# wa_psu.net
KiCad netlist of a schematic drawn in EAGLE
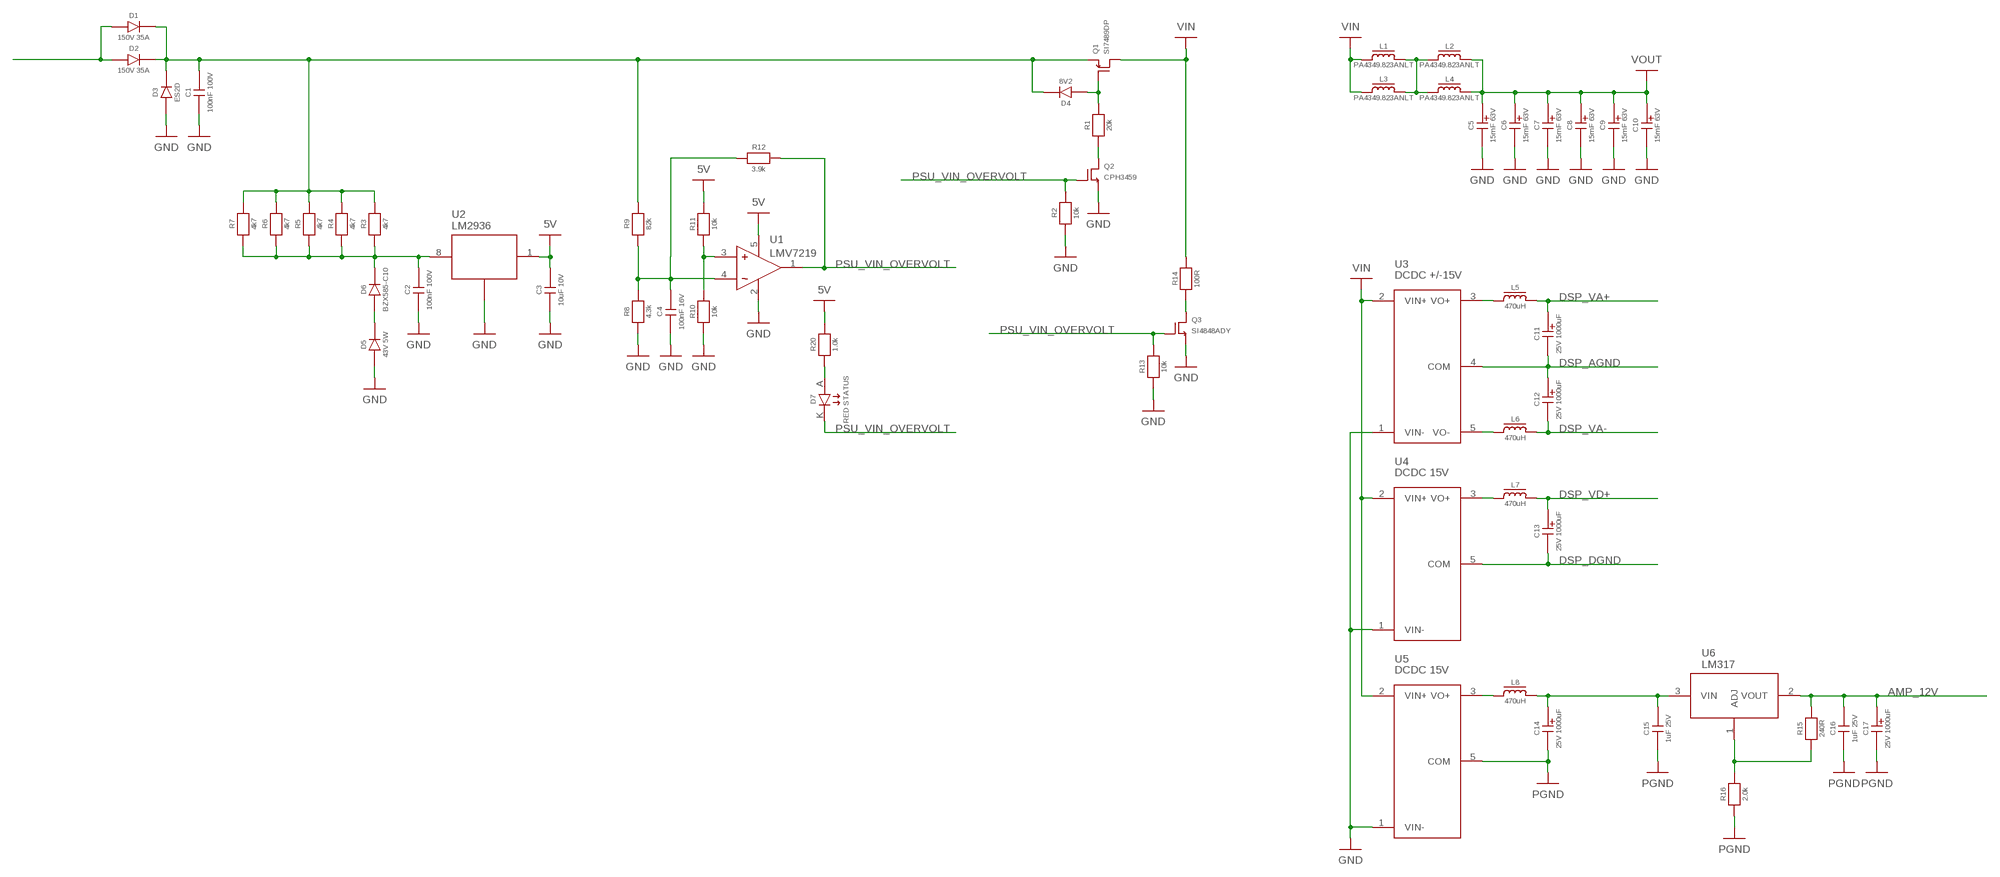
[diagram p0: schematic, sheet 1]

(export (version "E")
  (design (tool "Eeschema 10.0.6"))
  (components
    (comp (ref "C1")
      (value "100nF 100V")
      (footprint "eagle-import:0603")
      (libsource (lib "eagle-import") (part "06031C104KAT2A"))
    )
    (comp (ref "C2")
      (value "100nF 100V")
      (footprint "eagle-import:0603")
      (libsource (lib "eagle-import") (part "06031C104KAT2A"))
    )
    (comp (ref "C3")
      (value "10uF 10V")
      (footprint "eagle-import:0603")
      (libsource (lib "eagle-import") (part "GRM188R61A106KE69D"))
    )
    (comp (ref "C4")
      (value "100nF 16V")
      (footprint "eagle-import:0603")
      (libsource (lib "eagle-import") (part "CL10B104KO8WPNC"))
    )
    (comp (ref "C5")
      (value "15mF 63V")
      (footprint "eagle-import:35MM_10MMCAP")
      (libsource (lib "eagle-import") (part "C_ELEC35MM"))
    )
    (comp (ref "C6")
      (value "15mF 63V")
      (footprint "eagle-import:35MM_10MMCAP")
      (libsource (lib "eagle-import") (part "C_ELEC35MM"))
    )
    (comp (ref "C7")
      (value "15mF 63V")
      (footprint "eagle-import:35MM_10MMCAP")
      (libsource (lib "eagle-import") (part "C_ELEC35MM"))
    )
    (comp (ref "C8")
      (value "15mF 63V")
      (footprint "eagle-import:35MM_10MMCAP")
      (libsource (lib "eagle-import") (part "C_ELEC35MM"))
    )
    (comp (ref "C9")
      (value "15mF 63V")
      (footprint "eagle-import:35MM_10MMCAP")
      (libsource (lib "eagle-import") (part "C_ELEC35MM"))
    )
    (comp (ref "C10")
      (value "15mF 63V")
      (footprint "eagle-import:35MM_10MMCAP")
      (libsource (lib "eagle-import") (part "C_ELEC35MM"))
    )
    (comp (ref "C11")
      (value "25V 1000uF")
      (footprint "eagle-import:10MM_RADIAL_5MM_PITCH")
      (libsource (lib "eagle-import") (part "25ZLJ1000M10X20"))
    )
    (comp (ref "C12")
      (value "25V 1000uF")
      (footprint "eagle-import:10MM_RADIAL_5MM_PITCH")
      (libsource (lib "eagle-import") (part "25ZLJ1000M10X20"))
    )
    (comp (ref "C13")
      (value "25V 1000uF")
      (footprint "eagle-import:10MM_RADIAL_5MM_PITCH")
      (libsource (lib "eagle-import") (part "25ZLJ1000M10X20"))
    )
    (comp (ref "C14")
      (value "25V 1000uF")
      (footprint "eagle-import:10MM_RADIAL_5MM_PITCH")
      (libsource (lib "eagle-import") (part "25ZLJ1000M10X20"))
    )
    (comp (ref "C15")
      (value "1uF 25V")
      (footprint "eagle-import:0603")
      (libsource (lib "eagle-import") (part "CL10A105KA8NNNC"))
    )
    (comp (ref "C16")
      (value "1uF 25V")
      (footprint "eagle-import:0603")
      (libsource (lib "eagle-import") (part "CL10A105KA8NNNC"))
    )
    (comp (ref "C17")
      (value "25V 1000uF")
      (footprint "eagle-import:10MM_RADIAL_5MM_PITCH")
      (libsource (lib "eagle-import") (part "25ZLJ1000M10X20"))
    )
    (comp (ref "D1")
      (value "150V 35A")
      (footprint "eagle-import:TO252")
      (libsource (lib "eagle-import") (part "V35PW15-M3/I"))
    )
    (comp (ref "D2")
      (value "150V 35A")
      (footprint "eagle-import:TO252")
      (libsource (lib "eagle-import") (part "V35PW15-M3/I"))
    )
    (comp (ref "D3")
      (value "ES2D")
      (footprint "eagle-import:DO214AA")
      (libsource (lib "eagle-import") (part "ES2D"))
    )
    (comp (ref "D4")
      (value "8V2")
      (footprint "eagle-import:SOD80")
      (libsource (lib "eagle-import") (part "BZT55C8V2"))
    )
    (comp (ref "D5")
      (value "43V 5W")
      (footprint "eagle-import:017AA-01")
      (libsource (lib "eagle-import") (part "1N5367BG"))
    )
    (comp (ref "D6")
      (value "BZX585-C10")
      (footprint "eagle-import:SOD_523")
      (libsource (lib "eagle-import") (part "BZX585-C10"))
    )
    (comp (ref "D7")
      (value "RED STATUS")
      (footprint "eagle-import:VLMT3100")
      (libsource (lib "eagle-import") (part "VLMT3100-GS08"))
    )
    (comp (ref "L1")
      (value "PA4349.823ANLT")
      (footprint "eagle-import:PA4349.ZZZANLT")
      (libsource (lib "eagle-import") (part "PA4349.823ANLT"))
    )
    (comp (ref "L2")
      (value "PA4349.823ANLT")
      (footprint "eagle-import:PA4349.ZZZANLT")
      (libsource (lib "eagle-import") (part "PA4349.823ANLT"))
    )
    (comp (ref "L3")
      (value "PA4349.823ANLT")
      (footprint "eagle-import:PA4349.ZZZANLT")
      (libsource (lib "eagle-import") (part "PA4349.823ANLT"))
    )
    (comp (ref "L4")
      (value "PA4349.823ANLT")
      (footprint "eagle-import:PA4349.ZZZANLT")
      (libsource (lib "eagle-import") (part "PA4349.823ANLT"))
    )
    (comp (ref "L5")
      (value "470uH")
      (footprint "eagle-import:SRN1060")
      (libsource (lib "eagle-import") (part "SRN1060-471M"))
    )
    (comp (ref "L6")
      (value "470uH")
      (footprint "eagle-import:SRN1060")
      (libsource (lib "eagle-import") (part "SRN1060-471M"))
    )
    (comp (ref "L7")
      (value "470uH")
      (footprint "eagle-import:SRN1060")
      (libsource (lib "eagle-import") (part "SRN1060-471M"))
    )
    (comp (ref "L8")
      (value "470uH")
      (footprint "eagle-import:SRN1060")
      (libsource (lib "eagle-import") (part "SRN1060-471M"))
    )
    (comp (ref "Q1")
      (value "SI7489DP")
      (footprint "eagle-import:SO8_POWERPAK")
      (libsource (lib "eagle-import") (part "SI7489DP-T1-E3"))
    )
    (comp (ref "Q2")
      (value "CPH3459")
      (footprint "eagle-import:SOT23-3")
      (libsource (lib "eagle-import") (part "CPH3459-TL-W"))
    )
    (comp (ref "Q3")
      (value "SI4848ADY")
      (footprint "eagle-import:SO8")
      (libsource (lib "eagle-import") (part "SI4848ADY-T1-GE3"))
    )
    (comp (ref "R1")
      (value "20k")
      (footprint "eagle-import:0603")
      (libsource (lib "eagle-import") (part "ERJ3EKF2002V"))
    )
    (comp (ref "R2")
      (value "10k")
      (footprint "eagle-import:0603")
      (libsource (lib "eagle-import") (part "ERJ3EKF1002V"))
    )
    (comp (ref "R3")
      (value "4k7")
      (footprint "eagle-import:1206")
      (libsource (lib "eagle-import") (part "CRCW12064K70FKEAHP"))
    )
    (comp (ref "R4")
      (value "4k7")
      (footprint "eagle-import:1206")
      (libsource (lib "eagle-import") (part "CRCW12064K70FKEAHP"))
    )
    (comp (ref "R5")
      (value "4k7")
      (footprint "eagle-import:1206")
      (libsource (lib "eagle-import") (part "CRCW12064K70FKEAHP"))
    )
    (comp (ref "R6")
      (value "4k7")
      (footprint "eagle-import:1206")
      (libsource (lib "eagle-import") (part "CRCW12064K70FKEAHP"))
    )
    (comp (ref "R7")
      (value "4k7")
      (footprint "eagle-import:1206")
      (libsource (lib "eagle-import") (part "CRCW12064K70FKEAHP"))
    )
    (comp (ref "R8")
      (value "4.3k")
      (footprint "eagle-import:0603")
      (libsource (lib "eagle-import") (part "ERJ3EKF4301V"))
    )
    (comp (ref "R9")
      (value "82k")
      (footprint "eagle-import:0603")
      (libsource (lib "eagle-import") (part "ERJ3EKF8202V"))
    )
    (comp (ref "R10")
      (value "10k")
      (footprint "eagle-import:0603")
      (libsource (lib "eagle-import") (part "ERJ3EKF1002V"))
    )
    (comp (ref "R11")
      (value "10k")
      (footprint "eagle-import:0603")
      (libsource (lib "eagle-import") (part "ERJ3EKF1002V"))
    )
    (comp (ref "R12")
      (value "3.9k")
      (footprint "eagle-import:0603")
      (libsource (lib "eagle-import") (part "ERJ3EKF3901V"))
    )
    (comp (ref "R13")
      (value "10k")
      (footprint "eagle-import:0603")
      (libsource (lib "eagle-import") (part "ERJ3EKF1002V"))
    )
    (comp (ref "R14")
      (value "100R")
      (footprint "eagle-import:15MM_TH")
      (libsource (lib "eagle-import") (part "ERG-3SJ101V"))
    )
    (comp (ref "R15")
      (value "240R")
      (footprint "eagle-import:0603")
      (libsource (lib "eagle-import") (part "ERJ3EKF2400V"))
    )
    (comp (ref "R16")
      (value "2.0k")
      (footprint "eagle-import:0603")
      (libsource (lib "eagle-import") (part "ERJ3EKF2001V"))
    )
    (comp (ref "R20")
      (value "1.0k")
      (footprint "eagle-import:0402")
      (libsource (lib "eagle-import") (part "ERJ-2RKF1001X"))
    )
    (comp (ref "U1")
      (value "LMV7219")
      (footprint "eagle-import:SOT23-5")
      (libsource (lib "eagle-import") (part "LMV7219M5/NOPB"))
    )
    (comp (ref "U2")
      (value "LM2936")
      (footprint "eagle-import:SO8")
      (libsource (lib "eagle-import") (part "LM2936HVMAX"))
    )
    (comp (ref "U3")
      (value "DCDC +/-15V")
      (footprint "eagle-import:PDQE10")
      (libsource (lib "eagle-import") (part "PDQE10-Q48-D15-D"))
    )
    (comp (ref "U4")
      (value "DCDC 15V")
      (footprint "eagle-import:PDQE10")
      (libsource (lib "eagle-import") (part "PDQE10-Q48-S15"))
    )
    (comp (ref "U5")
      (value "DCDC 15V")
      (footprint "eagle-import:PDQE10")
      (libsource (lib "eagle-import") (part "PDQE10-Q48-S15"))
    )
    (comp (ref "U6")
      (value "LM317")
      (footprint "eagle-import:TO220")
      (libsource (lib "eagle-import") (part "LM317T"))
    )
  )
  (nets
    (net (code "1") (name "/AMP_12V") (class "Default")
      (node (ref "C16") (pin "2") (pinfunction "2_2") (pintype "bidirectional"))
      (node (ref "C17") (pin "2") (pinfunction "A_2") (pintype "bidirectional"))
      (node (ref "R15") (pin "2") (pinfunction "2_2") (pintype "bidirectional"))
      (node (ref "U6") (pin "2") (pinfunction "VOUT_2") (pintype "bidirectional"))
    )
    (net (code "2") (name "/DSP_AGND") (class "Default")
      (node (ref "C11") (pin "1") (pinfunction "K_1") (pintype "bidirectional"))
      (node (ref "C12") (pin "2") (pinfunction "A_2") (pintype "bidirectional"))
      (node (ref "U3") (pin "4") (pinfunction "COM_4") (pintype "bidirectional"))
    )
    (net (code "3") (name "/DSP_DGND") (class "Default")
      (node (ref "C13") (pin "1") (pinfunction "K_1") (pintype "bidirectional"))
      (node (ref "U4") (pin "5") (pinfunction "COM_5") (pintype "bidirectional"))
    )
    (net (code "4") (name "/DSP_VA+") (class "Default")
      (node (ref "C11") (pin "2") (pinfunction "A_2") (pintype "bidirectional"))
      (node (ref "L5") (pin "2") (pinfunction "2_2") (pintype "bidirectional"))
    )
    (net (code "5") (name "/DSP_VA-") (class "Default")
      (node (ref "C12") (pin "1") (pinfunction "K_1") (pintype "bidirectional"))
      (node (ref "L6") (pin "2") (pinfunction "2_2") (pintype "bidirectional"))
    )
    (net (code "6") (name "/DSP_VD+") (class "Default")
      (node (ref "C13") (pin "2") (pinfunction "A_2") (pintype "bidirectional"))
      (node (ref "L7") (pin "2") (pinfunction "2_2") (pintype "bidirectional"))
    )
    (net (code "7") (name "/PSU_VIN_OVERVOLT") (class "Default")
      (node (ref "D7") (pin "K") (pinfunction "K_K") (pintype "bidirectional"))
      (node (ref "Q2") (pin "1") (pinfunction "G_1") (pintype "bidirectional"))
      (node (ref "Q3") (pin "4") (pinfunction "G_4") (pintype "bidirectional"))
      (node (ref "R12") (pin "2") (pinfunction "2_2") (pintype "bidirectional"))
      (node (ref "R13") (pin "2") (pinfunction "2_2") (pintype "bidirectional"))
      (node (ref "R2") (pin "2") (pinfunction "2_2") (pintype "bidirectional"))
      (node (ref "U1") (pin "1") (pinfunction "VOUT_1") (pintype "bidirectional"))
    )
    (net (code "8") (name "5V") (class "Default")
      (node (ref "C3") (pin "2") (pinfunction "2_2") (pintype "bidirectional"))
      (node (ref "R11") (pin "2") (pinfunction "2_2") (pintype "bidirectional"))
      (node (ref "R20") (pin "2") (pinfunction "2_2") (pintype "bidirectional"))
      (node (ref "U1") (pin "5") (pinfunction "VCC_5") (pintype "bidirectional"))
      (node (ref "U2") (pin "1") (pinfunction "VOUT_1") (pintype "bidirectional"))
    )
    (net (code "9") (name "GND") (class "Default")
      (node (ref "C1") (pin "1") (pinfunction "1_1") (pintype "bidirectional"))
      (node (ref "C10") (pin "P$2") (pinfunction "2_P$2") (pintype "bidirectional"))
      (node (ref "C2") (pin "1") (pinfunction "1_1") (pintype "bidirectional"))
      (node (ref "C3") (pin "1") (pinfunction "1_1") (pintype "bidirectional"))
      (node (ref "C4") (pin "1") (pinfunction "1_1") (pintype "bidirectional"))
      (node (ref "C5") (pin "P$2") (pinfunction "2_P$2") (pintype "bidirectional"))
      (node (ref "C6") (pin "P$2") (pinfunction "2_P$2") (pintype "bidirectional"))
      (node (ref "C7") (pin "P$2") (pinfunction "2_P$2") (pintype "bidirectional"))
      (node (ref "C8") (pin "P$2") (pinfunction "2_P$2") (pintype "bidirectional"))
      (node (ref "C9") (pin "P$2") (pinfunction "2_P$2") (pintype "bidirectional"))
      (node (ref "D3") (pin "A") (pinfunction "A_A") (pintype "bidirectional"))
      (node (ref "D5") (pin "A") (pinfunction "A_A") (pintype "bidirectional"))
      (node (ref "Q2") (pin "3") (pinfunction "S_3") (pintype "bidirectional"))
      (node (ref "Q3") (pin "1") (pinfunction "S_1") (pintype "bidirectional"))
      (node (ref "Q3") (pin "2") (pinfunction "S_2") (pintype "bidirectional"))
      (node (ref "Q3") (pin "3") (pinfunction "S_3") (pintype "bidirectional"))
      (node (ref "R10") (pin "1") (pinfunction "1_1") (pintype "bidirectional"))
      (node (ref "R13") (pin "1") (pinfunction "1_1") (pintype "bidirectional"))
      (node (ref "R2") (pin "1") (pinfunction "1_1") (pintype "bidirectional"))
      (node (ref "R8") (pin "1") (pinfunction "1_1") (pintype "bidirectional"))
      (node (ref "U1") (pin "2") (pinfunction "GND_2") (pintype "bidirectional"))
      (node (ref "U2") (pin "2") (pinfunction "GND_2") (pintype "bidirectional"))
      (node (ref "U2") (pin "3") (pinfunction "GND_3") (pintype "bidirectional"))
      (node (ref "U2") (pin "6") (pinfunction "GND_6") (pintype "bidirectional"))
      (node (ref "U2") (pin "7") (pinfunction "GND_7") (pintype "bidirectional"))
      (node (ref "U3") (pin "1") (pinfunction "VIN-_1") (pintype "bidirectional"))
      (node (ref "U4") (pin "1") (pinfunction "VIN-_1") (pintype "bidirectional"))
      (node (ref "U5") (pin "1") (pinfunction "VIN-_1") (pintype "bidirectional"))
    )
    (net (code "10") (name "Net-(C14-A)") (class "Default")
      (node (ref "C14") (pin "2") (pinfunction "A_2") (pintype "bidirectional"))
      (node (ref "C15") (pin "2") (pinfunction "2_2") (pintype "bidirectional"))
      (node (ref "L8") (pin "2") (pinfunction "2_2") (pintype "bidirectional"))
      (node (ref "U6") (pin "3") (pinfunction "VIN_3") (pintype "bidirectional"))
    )
    (net (code "11") (name "Net-(D1-A-Pad1)") (class "Default")
      (node (ref "D1") (pin "1") (pinfunction "A_1") (pintype "bidirectional"))
      (node (ref "D1") (pin "3") (pinfunction "A_3") (pintype "bidirectional"))
      (node (ref "D2") (pin "1") (pinfunction "A_1") (pintype "bidirectional"))
      (node (ref "D2") (pin "3") (pinfunction "A_3") (pintype "bidirectional"))
    )
    (net (code "12") (name "Net-(D1-K)") (class "Default")
      (node (ref "C1") (pin "2") (pinfunction "2_2") (pintype "bidirectional"))
      (node (ref "D1") (pin "4") (pinfunction "K_4") (pintype "bidirectional"))
      (node (ref "D2") (pin "4") (pinfunction "K_4") (pintype "bidirectional"))
      (node (ref "D3") (pin "K") (pinfunction "K_K") (pintype "bidirectional"))
      (node (ref "D4") (pin "K") (pinfunction "K_K") (pintype "bidirectional"))
      (node (ref "Q1") (pin "1") (pinfunction "S_1") (pintype "bidirectional"))
      (node (ref "Q1") (pin "2") (pinfunction "S_2") (pintype "bidirectional"))
      (node (ref "Q1") (pin "3") (pinfunction "S_3") (pintype "bidirectional"))
      (node (ref "R3") (pin "2") (pinfunction "2_2") (pintype "bidirectional"))
      (node (ref "R4") (pin "2") (pinfunction "2_2") (pintype "bidirectional"))
      (node (ref "R5") (pin "2") (pinfunction "2_2") (pintype "bidirectional"))
      (node (ref "R6") (pin "2") (pinfunction "2_2") (pintype "bidirectional"))
      (node (ref "R7") (pin "2") (pinfunction "2_2") (pintype "bidirectional"))
      (node (ref "R9") (pin "2") (pinfunction "2_2") (pintype "bidirectional"))
    )
    (net (code "13") (name "Net-(D5-PadK)") (class "Default")
      (node (ref "D5") (pin "K") (pinfunction "K_K") (pintype "bidirectional"))
      (node (ref "D6") (pin "A") (pinfunction "A_A") (pintype "bidirectional"))
    )
    (net (code "14") (name "Net-(D7-PadA)") (class "Default")
      (node (ref "D7") (pin "A") (pinfunction "A_A") (pintype "bidirectional"))
      (node (ref "R20") (pin "1") (pinfunction "1_1") (pintype "bidirectional"))
    )
    (net (code "15") (name "Net-(L1-Pad2)") (class "Default")
      (node (ref "L1") (pin "2") (pinfunction "2_2") (pintype "bidirectional"))
      (node (ref "L2") (pin "1") (pinfunction "1_1") (pintype "bidirectional"))
      (node (ref "L3") (pin "2") (pinfunction "2_2") (pintype "bidirectional"))
      (node (ref "L4") (pin "1") (pinfunction "1_1") (pintype "bidirectional"))
    )
    (net (code "16") (name "Net-(Q1-G)") (class "Default")
      (node (ref "D4") (pin "A") (pinfunction "A_A") (pintype "bidirectional"))
      (node (ref "Q1") (pin "4") (pinfunction "G_4") (pintype "bidirectional"))
      (node (ref "R1") (pin "2") (pinfunction "2_2") (pintype "bidirectional"))
    )
    (net (code "17") (name "Net-(Q2-D)") (class "Default")
      (node (ref "Q2") (pin "2") (pinfunction "D_2") (pintype "bidirectional"))
      (node (ref "R1") (pin "1") (pinfunction "1_1") (pintype "bidirectional"))
    )
    (net (code "18") (name "Net-(Q3-D-Pad5)") (class "Default")
      (node (ref "Q3") (pin "5") (pinfunction "D_5") (pintype "bidirectional"))
      (node (ref "Q3") (pin "6") (pinfunction "D_6") (pintype "bidirectional"))
      (node (ref "Q3") (pin "7") (pinfunction "D_7") (pintype "bidirectional"))
      (node (ref "Q3") (pin "8") (pinfunction "D_8") (pintype "bidirectional"))
      (node (ref "R14") (pin "1") (pinfunction "1_1") (pintype "bidirectional"))
    )
    (net (code "19") (name "Net-(U1-+)") (class "Default")
      (node (ref "R10") (pin "2") (pinfunction "2_2") (pintype "bidirectional"))
      (node (ref "R11") (pin "1") (pinfunction "1_1") (pintype "bidirectional"))
      (node (ref "U1") (pin "3") (pinfunction "+_3") (pintype "bidirectional"))
    )
    (net (code "20") (name "Net-(U1--)") (class "Default")
      (node (ref "C4") (pin "2") (pinfunction "2_2") (pintype "bidirectional"))
      (node (ref "R12") (pin "1") (pinfunction "1_1") (pintype "bidirectional"))
      (node (ref "R8") (pin "2") (pinfunction "2_2") (pintype "bidirectional"))
      (node (ref "R9") (pin "1") (pinfunction "1_1") (pintype "bidirectional"))
      (node (ref "U1") (pin "4") (pinfunction "-_4") (pintype "bidirectional"))
    )
    (net (code "21") (name "Net-(U2-VIN)") (class "Default")
      (node (ref "C2") (pin "2") (pinfunction "2_2") (pintype "bidirectional"))
      (node (ref "D6") (pin "K") (pinfunction "K_K") (pintype "bidirectional"))
      (node (ref "R3") (pin "1") (pinfunction "1_1") (pintype "bidirectional"))
      (node (ref "R4") (pin "1") (pinfunction "1_1") (pintype "bidirectional"))
      (node (ref "R5") (pin "1") (pinfunction "1_1") (pintype "bidirectional"))
      (node (ref "R6") (pin "1") (pinfunction "1_1") (pintype "bidirectional"))
      (node (ref "R7") (pin "1") (pinfunction "1_1") (pintype "bidirectional"))
      (node (ref "U2") (pin "8") (pinfunction "VIN_8") (pintype "bidirectional"))
    )
    (net (code "22") (name "Net-(U3-VO+)") (class "Default")
      (node (ref "L5") (pin "1") (pinfunction "1_1") (pintype "bidirectional"))
      (node (ref "U3") (pin "3") (pinfunction "VO+_3") (pintype "bidirectional"))
    )
    (net (code "23") (name "Net-(U3-VO-)") (class "Default")
      (node (ref "L6") (pin "1") (pinfunction "1_1") (pintype "bidirectional"))
      (node (ref "U3") (pin "5") (pinfunction "VO-_5") (pintype "bidirectional"))
    )
    (net (code "24") (name "Net-(U4-VO+)") (class "Default")
      (node (ref "L7") (pin "1") (pinfunction "1_1") (pintype "bidirectional"))
      (node (ref "U4") (pin "3") (pinfunction "VO+_3") (pintype "bidirectional"))
    )
    (net (code "25") (name "Net-(U5-VO+)") (class "Default")
      (node (ref "L8") (pin "1") (pinfunction "1_1") (pintype "bidirectional"))
      (node (ref "U5") (pin "3") (pinfunction "VO+_3") (pintype "bidirectional"))
    )
    (net (code "26") (name "Net-(U6-ADJ)") (class "Default")
      (node (ref "R15") (pin "1") (pinfunction "1_1") (pintype "bidirectional"))
      (node (ref "R16") (pin "2") (pinfunction "2_2") (pintype "bidirectional"))
      (node (ref "U6") (pin "1") (pinfunction "ADJ_1") (pintype "bidirectional"))
    )
    (net (code "27") (name "PGND") (class "Default")
      (node (ref "C14") (pin "1") (pinfunction "K_1") (pintype "bidirectional"))
      (node (ref "C15") (pin "1") (pinfunction "1_1") (pintype "bidirectional"))
      (node (ref "C16") (pin "1") (pinfunction "1_1") (pintype "bidirectional"))
      (node (ref "C17") (pin "1") (pinfunction "K_1") (pintype "bidirectional"))
      (node (ref "R16") (pin "1") (pinfunction "1_1") (pintype "bidirectional"))
      (node (ref "U5") (pin "5") (pinfunction "COM_5") (pintype "bidirectional"))
    )
    (net (code "28") (name "VIN") (class "Default")
      (node (ref "L1") (pin "1") (pinfunction "1_1") (pintype "bidirectional"))
      (node (ref "L3") (pin "1") (pinfunction "1_1") (pintype "bidirectional"))
      (node (ref "Q1") (pin "5") (pinfunction "D_5") (pintype "bidirectional"))
      (node (ref "Q1") (pin "6") (pinfunction "D_6") (pintype "bidirectional"))
      (node (ref "Q1") (pin "7") (pinfunction "D_7") (pintype "bidirectional"))
      (node (ref "Q1") (pin "8") (pinfunction "D_8") (pintype "bidirectional"))
      (node (ref "Q1") (pin "PAD") (pinfunction "D_PAD") (pintype "bidirectional"))
      (node (ref "R14") (pin "2") (pinfunction "2_2") (pintype "bidirectional"))
      (node (ref "U3") (pin "2") (pinfunction "VIN+_2") (pintype "bidirectional"))
      (node (ref "U4") (pin "2") (pinfunction "VIN+_2") (pintype "bidirectional"))
      (node (ref "U5") (pin "2") (pinfunction "VIN+_2") (pintype "bidirectional"))
    )
    (net (code "29") (name "VOUT") (class "Default")
      (node (ref "C10") (pin "P$1") (pinfunction "1_P$1") (pintype "bidirectional"))
      (node (ref "C5") (pin "P$1") (pinfunction "1_P$1") (pintype "bidirectional"))
      (node (ref "C6") (pin "P$1") (pinfunction "1_P$1") (pintype "bidirectional"))
      (node (ref "C7") (pin "P$1") (pinfunction "1_P$1") (pintype "bidirectional"))
      (node (ref "C8") (pin "P$1") (pinfunction "1_P$1") (pintype "bidirectional"))
      (node (ref "C9") (pin "P$1") (pinfunction "1_P$1") (pintype "bidirectional"))
      (node (ref "L2") (pin "2") (pinfunction "2_2") (pintype "bidirectional"))
      (node (ref "L4") (pin "2") (pinfunction "2_2") (pintype "bidirectional"))
    )
  )
)
